# EVK-IRIS-W1-MCULINK-MUX.net
KiCad netlist of a schematic drawn in Altium Designer
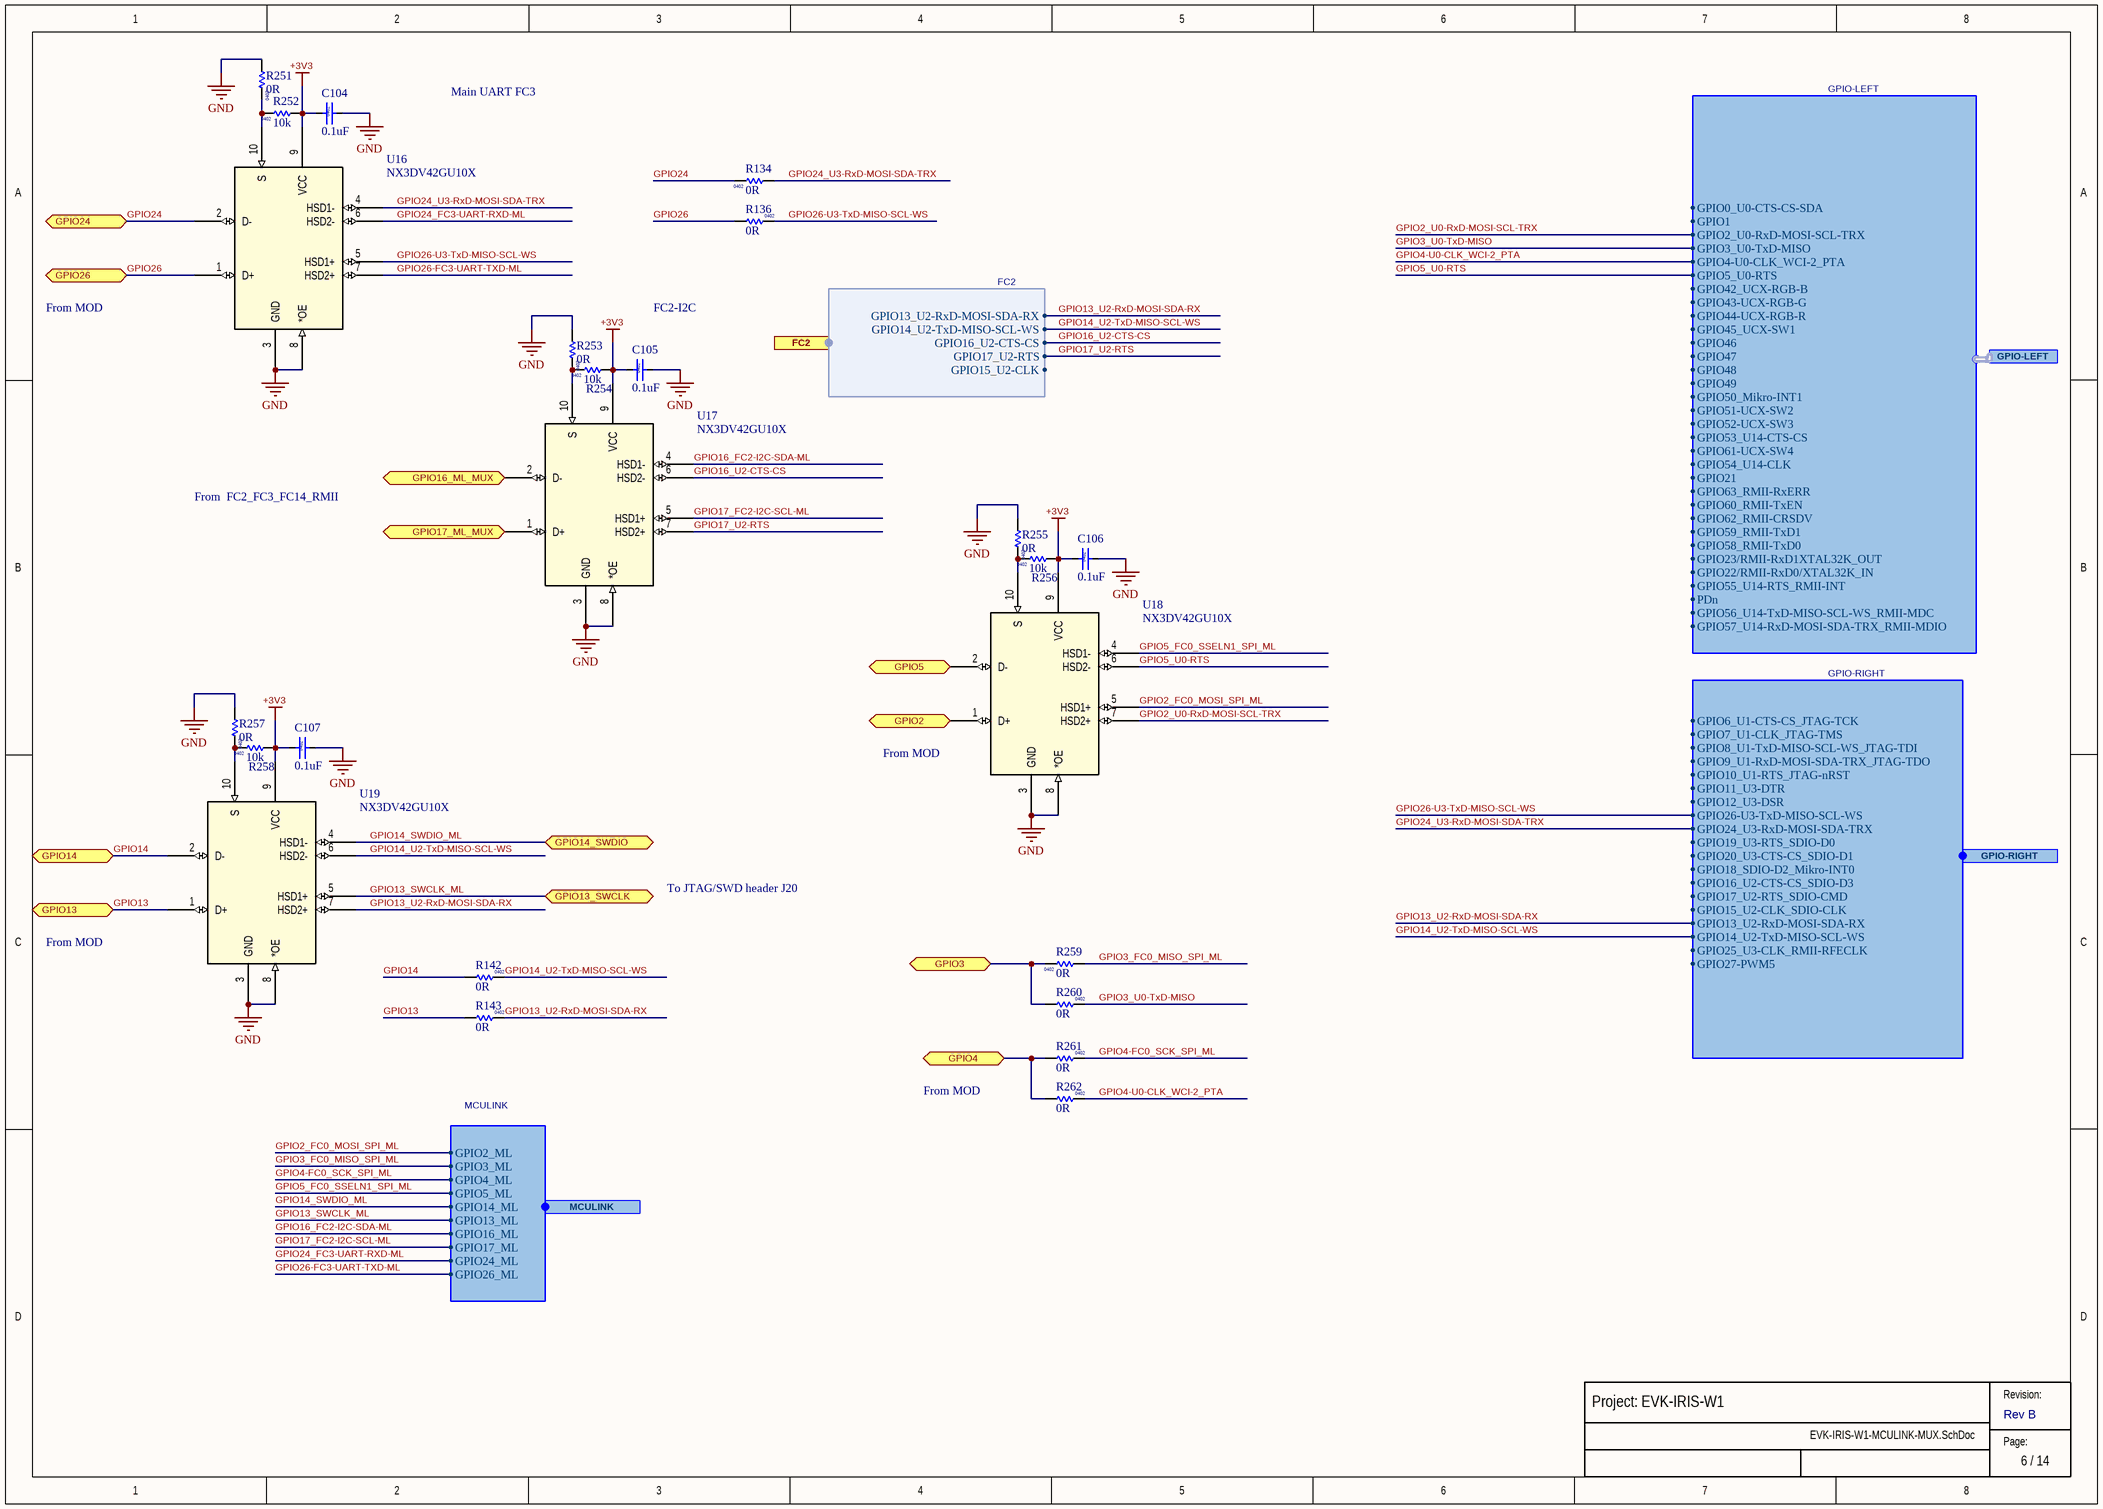
[diagram p0: EVK-IRIS-W1-MCULINK-MUX.SchDoc]

(export (version "E")
  (design (tool "Eeschema 10.0.6"))
  (components
    (comp (ref "C104")
      (value "0.1uF")
      (footprint "Cap 0402 HD")
      (description "Cap, Ceramic 0.1uF 10V 10% X5R 0402")
      (fields
        (field (name "SIZE") "0402")
        (field (name "PART NUMBER") "120-00016")
        (field (name "TOLERANCE") "+/- 10%")
      )
      (libsource (lib "Arena_Parts_DB_Lib") (part "Cap Chip"))
    )
    (comp (ref "C105")
      (value "0.1uF")
      (footprint "Cap 0402 HD")
      (description "Cap, Ceramic 0.1uF 10V 10% X5R 0402")
      (fields
        (field (name "SIZE") "0402")
        (field (name "PART NUMBER") "120-00016")
        (field (name "TOLERANCE") "+/- 10%")
      )
      (libsource (lib "Arena_Parts_DB_Lib") (part "Cap Chip"))
    )
    (comp (ref "C106")
      (value "0.1uF")
      (footprint "Cap 0402 HD")
      (description "Cap, Ceramic 0.1uF 10V 10% X5R 0402")
      (fields
        (field (name "SIZE") "0402")
        (field (name "PART NUMBER") "120-00016")
        (field (name "TOLERANCE") "+/- 10%")
      )
      (libsource (lib "Arena_Parts_DB_Lib") (part "Cap Chip"))
    )
    (comp (ref "C107")
      (value "0.1uF")
      (footprint "Cap 0402 HD")
      (description "Cap, Ceramic 0.1uF 10V 10% X5R 0402")
      (fields
        (field (name "SIZE") "0402")
        (field (name "PART NUMBER") "120-00016")
        (field (name "TOLERANCE") "+/- 10%")
      )
      (libsource (lib "Arena_Parts_DB_Lib") (part "Cap Chip"))
    )
    (comp (ref "R134")
      (value "0R")
      (footprint "RES 0402 HD")
      (description "RES THICK FILM CHIP 0402 0R 0 100mW")
      (fields
        (field (name "SIZE") "0402")
        (field (name "PART NUMBER") "UBXH18-0003002")
        (field (name "TOLERANCE") "0")
        (field (name "EDITOR") "charlotte.biber")
        (field (name "RELEASED BY") "peter.mueller")
      )
      (libsource (lib "UBX_Parts_DB_Lib") (part "Res sm"))
    )
    (comp (ref "R136")
      (value "0R")
      (footprint "RES 0402 HD")
      (description "RES THICK FILM CHIP 0402 0R 0 100mW")
      (fields
        (field (name "SIZE") "0402")
        (field (name "PART NUMBER") "UBXH18-0003002")
        (field (name "TOLERANCE") "0")
        (field (name "EDITOR") "charlotte.biber")
        (field (name "RELEASED BY") "peter.mueller")
      )
      (libsource (lib "UBX_Parts_DB_Lib") (part "Res sm"))
    )
    (comp (ref "R142")
      (value "0R")
      (footprint "RES 0402 HD")
      (description "RES THICK FILM CHIP 0402 0R 0 100mW")
      (fields
        (field (name "SIZE") "0402")
        (field (name "PART NUMBER") "UBXH18-0003002")
        (field (name "TOLERANCE") "0")
        (field (name "EDITOR") "charlotte.biber")
        (field (name "RELEASED BY") "peter.mueller")
      )
      (libsource (lib "UBX_Parts_DB_Lib") (part "Res sm"))
    )
    (comp (ref "R143")
      (value "0R")
      (footprint "RES 0402 HD")
      (description "RES THICK FILM CHIP 0402 0R 0 100mW")
      (fields
        (field (name "SIZE") "0402")
        (field (name "PART NUMBER") "UBXH18-0003002")
        (field (name "TOLERANCE") "0")
        (field (name "EDITOR") "charlotte.biber")
        (field (name "RELEASED BY") "peter.mueller")
      )
      (libsource (lib "UBX_Parts_DB_Lib") (part "Res sm"))
    )
    (comp (ref "R251")
      (value "0R")
      (footprint "RES 0402 HD")
      (description "RES THICK FILM CHIP 0402 0R 0 100mW")
      (fields
        (field (name "SIZE") "0402")
        (field (name "PART NUMBER") "UBXH18-0003002")
        (field (name "TOLERANCE") "0")
        (field (name "EDITOR") "charlotte.biber")
        (field (name "RELEASED BY") "peter.mueller")
      )
      (libsource (lib "UBX_Parts_DB_Lib") (part "Res sm"))
    )
    (comp (ref "R252")
      (value "10k")
      (footprint "RES 0402 HD")
      (description "Resistor 10k ohm 1% 1/16W, 0402")
      (fields
        (field (name "SIZE") "0402")
        (field (name "PART NUMBER") "180-00024")
        (field (name "POWER") "1/16W")
      )
      (libsource (lib "Arena_Parts_DB_Lib") (part "Res sm"))
    )
    (comp (ref "R253")
      (value "0R")
      (footprint "RES 0402 HD")
      (description "RES THICK FILM CHIP 0402 0R 0 100mW")
      (fields
        (field (name "SIZE") "0402")
        (field (name "PART NUMBER") "UBXH18-0003002")
        (field (name "TOLERANCE") "0")
        (field (name "EDITOR") "charlotte.biber")
        (field (name "RELEASED BY") "peter.mueller")
      )
      (libsource (lib "UBX_Parts_DB_Lib") (part "Res sm"))
    )
    (comp (ref "R254")
      (value "10k")
      (footprint "RES 0402 HD")
      (description "Resistor 10k ohm 1% 1/16W, 0402")
      (fields
        (field (name "SIZE") "0402")
        (field (name "PART NUMBER") "180-00024")
        (field (name "POWER") "1/16W")
      )
      (libsource (lib "Arena_Parts_DB_Lib") (part "Res sm"))
    )
    (comp (ref "R255")
      (value "0R")
      (footprint "RES 0402 HD")
      (description "RES THICK FILM CHIP 0402 0R 0 100mW")
      (fields
        (field (name "SIZE") "0402")
        (field (name "PART NUMBER") "UBXH18-0003002")
        (field (name "TOLERANCE") "0")
        (field (name "EDITOR") "charlotte.biber")
        (field (name "RELEASED BY") "peter.mueller")
      )
      (libsource (lib "UBX_Parts_DB_Lib") (part "Res sm"))
    )
    (comp (ref "R256")
      (value "10k")
      (footprint "RES 0402 HD")
      (description "Resistor 10k ohm 1% 1/16W, 0402")
      (fields
        (field (name "SIZE") "0402")
        (field (name "PART NUMBER") "180-00024")
        (field (name "POWER") "1/16W")
      )
      (libsource (lib "Arena_Parts_DB_Lib") (part "Res sm"))
    )
    (comp (ref "R257")
      (value "0R")
      (footprint "RES 0402 HD")
      (description "RES THICK FILM CHIP 0402 0R 0 100mW")
      (fields
        (field (name "SIZE") "0402")
        (field (name "PART NUMBER") "UBXH18-0003002")
        (field (name "TOLERANCE") "0")
        (field (name "EDITOR") "charlotte.biber")
        (field (name "RELEASED BY") "peter.mueller")
      )
      (libsource (lib "UBX_Parts_DB_Lib") (part "Res sm"))
    )
    (comp (ref "R258")
      (value "10k")
      (footprint "RES 0402 HD")
      (description "Resistor 10k ohm 1% 1/16W, 0402")
      (fields
        (field (name "SIZE") "0402")
        (field (name "PART NUMBER") "180-00024")
        (field (name "POWER") "1/16W")
      )
      (libsource (lib "Arena_Parts_DB_Lib") (part "Res sm"))
    )
    (comp (ref "R259")
      (value "0R")
      (footprint "RES 0402 HD")
      (description "RES THICK FILM CHIP 0402 0R 0 100mW")
      (fields
        (field (name "SIZE") "0402")
        (field (name "PART NUMBER") "UBXH18-0003002")
        (field (name "TOLERANCE") "0")
        (field (name "EDITOR") "charlotte.biber")
        (field (name "RELEASED BY") "peter.mueller")
      )
      (libsource (lib "UBX_Parts_DB_Lib") (part "Res sm"))
    )
    (comp (ref "R260")
      (value "0R")
      (footprint "RES 0402 HD")
      (description "RES THICK FILM CHIP 0402 0R 0 100mW")
      (fields
        (field (name "SIZE") "0402")
        (field (name "PART NUMBER") "UBXH18-0003002")
        (field (name "TOLERANCE") "0")
        (field (name "EDITOR") "charlotte.biber")
        (field (name "RELEASED BY") "peter.mueller")
      )
      (libsource (lib "UBX_Parts_DB_Lib") (part "Res sm"))
    )
    (comp (ref "R261")
      (value "0R")
      (footprint "RES 0402 HD")
      (description "RES THICK FILM CHIP 0402 0R 0 100mW")
      (fields
        (field (name "SIZE") "0402")
        (field (name "PART NUMBER") "UBXH18-0003002")
        (field (name "TOLERANCE") "0")
        (field (name "EDITOR") "charlotte.biber")
        (field (name "RELEASED BY") "peter.mueller")
      )
      (libsource (lib "UBX_Parts_DB_Lib") (part "Res sm"))
    )
    (comp (ref "R262")
      (value "0R")
      (footprint "RES 0402 HD")
      (description "RES THICK FILM CHIP 0402 0R 0 100mW")
      (fields
        (field (name "SIZE") "0402")
        (field (name "PART NUMBER") "UBXH18-0003002")
        (field (name "TOLERANCE") "0")
        (field (name "EDITOR") "charlotte.biber")
        (field (name "RELEASED BY") "peter.mueller")
      )
      (libsource (lib "UBX_Parts_DB_Lib") (part "Res sm"))
    )
    (comp (ref "U16")
      (value "NX3DV42GU10X")
      (footprint "XQFN10_SOT1337-1_NXP")
      (description "No Description Available")
      (fields (field (name "COPYRIGHT") "Copyright (C) 2023 Ultra Librarian. All rights reserved."))
      (libsource (lib "NX3DV42GU10X") (part "NX3DV42GU10X"))
    )
    (comp (ref "U17")
      (value "NX3DV42GU10X")
      (footprint "XQFN10_SOT1337-1_NXP")
      (description "No Description Available")
      (fields (field (name "COPYRIGHT") "Copyright (C) 2023 Ultra Librarian. All rights reserved."))
      (libsource (lib "NX3DV42GU10X") (part "NX3DV42GU10X"))
    )
    (comp (ref "U18")
      (value "NX3DV42GU10X")
      (footprint "XQFN10_SOT1337-1_NXP")
      (description "No Description Available")
      (fields (field (name "COPYRIGHT") "Copyright (C) 2023 Ultra Librarian. All rights reserved."))
      (libsource (lib "NX3DV42GU10X") (part "NX3DV42GU10X"))
    )
    (comp (ref "U19")
      (value "NX3DV42GU10X")
      (footprint "XQFN10_SOT1337-1_NXP")
      (description "No Description Available")
      (fields (field (name "COPYRIGHT") "Copyright (C) 2023 Ultra Librarian. All rights reserved."))
      (libsource (lib "NX3DV42GU10X") (part "NX3DV42GU10X"))
    )
  )
  (nets
    (net (code "5") (name "+3V3") (class "Default")
      (node (ref "C104") (pin "1") (pinfunction "1_1") (pintype "passive"))
      (node (ref "C105") (pin "1") (pinfunction "1_1") (pintype "passive"))
      (node (ref "C106") (pin "1") (pinfunction "1_1") (pintype "passive"))
      (node (ref "C107") (pin "1") (pinfunction "1_1") (pintype "passive"))
      (node (ref "R252") (pin "1") (pinfunction "1_1") (pintype "passive"))
      (node (ref "R254") (pin "1") (pinfunction "1_1") (pintype "passive"))
      (node (ref "R256") (pin "1") (pinfunction "1_1") (pintype "passive"))
      (node (ref "R258") (pin "1") (pinfunction "1_1") (pintype "passive"))
      (node (ref "U16") (pin "9") (pinfunction "VCC_9") (pintype "power_in"))
      (node (ref "U17") (pin "9") (pinfunction "VCC_9") (pintype "power_in"))
      (node (ref "U18") (pin "9") (pinfunction "VCC_9") (pintype "power_in"))
      (node (ref "U19") (pin "9") (pinfunction "VCC_9") (pintype "power_in"))
    )
    (net (code "6") (name "/GPIO2") (class "Default")
      (node (ref "U18") (pin "1") (pinfunction "D+_1") (pintype "bidirectional"))
    )
    (net (code "7") (name "/GPIO2_FC0_MOSI_SPI_ML") (class "Default")
      (node (ref "U18") (pin "5") (pinfunction "HSD1+_5") (pintype "bidirectional"))
    )
    (net (code "8") (name "/GPIO2_U0-RxD-MOSI-SCL-TRX") (class "Default")
      (node (ref "U18") (pin "7") (pinfunction "HSD2+_7") (pintype "bidirectional"))
    )
    (net (code "9") (name "/GPIO3") (class "Default")
      (node (ref "R259") (pin "2") (pinfunction "2_2") (pintype "passive"))
      (node (ref "R260") (pin "1") (pinfunction "1_1") (pintype "passive"))
    )
    (net (code "10") (name "/GPIO3_FC0_MISO_SPI_ML") (class "Default")
      (node (ref "R259") (pin "1") (pinfunction "1_1") (pintype "passive"))
    )
    (net (code "11") (name "/GPIO3_U0-TxD-MISO") (class "Default")
      (node (ref "R260") (pin "2") (pinfunction "2_2") (pintype "passive"))
    )
    (net (code "12") (name "/GPIO4") (class "Default")
      (node (ref "R261") (pin "1") (pinfunction "1_1") (pintype "passive"))
      (node (ref "R262") (pin "1") (pinfunction "1_1") (pintype "passive"))
    )
    (net (code "13") (name "/GPIO4-FC0_SCK_SPI_ML") (class "Default")
      (node (ref "R261") (pin "2") (pinfunction "2_2") (pintype "passive"))
    )
    (net (code "14") (name "/GPIO4-U0-CLK_WCI-2_PTA") (class "Default")
      (node (ref "R262") (pin "2") (pinfunction "2_2") (pintype "passive"))
    )
    (net (code "15") (name "/GPIO5") (class "Default")
      (node (ref "U18") (pin "2") (pinfunction "D-_2") (pintype "bidirectional"))
    )
    (net (code "16") (name "/GPIO5_FC0_SSELN1_SPI_ML") (class "Default")
      (node (ref "U18") (pin "4") (pinfunction "HSD1-_4") (pintype "bidirectional"))
    )
    (net (code "17") (name "/GPIO5_U0-RTS") (class "Default")
      (node (ref "U18") (pin "6") (pinfunction "HSD2-_6") (pintype "bidirectional"))
    )
    (net (code "18") (name "/GPIO13") (class "Default")
      (node (ref "R143") (pin "1") (pinfunction "1_1") (pintype "passive"))
      (node (ref "U19") (pin "1") (pinfunction "D+_1") (pintype "bidirectional"))
    )
    (net (code "19") (name "/GPIO13_SWCLK_ML") (class "Default")
      (node (ref "U19") (pin "5") (pinfunction "HSD1+_5") (pintype "bidirectional"))
    )
    (net (code "20") (name "/GPIO13_U2-RxD-MOSI-SDA-RX") (class "Default")
      (node (ref "R143") (pin "2") (pinfunction "2_2") (pintype "passive"))
      (node (ref "U19") (pin "7") (pinfunction "HSD2+_7") (pintype "bidirectional"))
    )
    (net (code "21") (name "/GPIO14") (class "Default")
      (node (ref "R142") (pin "1") (pinfunction "1_1") (pintype "passive"))
      (node (ref "U19") (pin "2") (pinfunction "D-_2") (pintype "bidirectional"))
    )
    (net (code "22") (name "/GPIO14_SWDIO_ML") (class "Default")
      (node (ref "U19") (pin "4") (pinfunction "HSD1-_4") (pintype "bidirectional"))
    )
    (net (code "23") (name "/GPIO14_U2-TxD-MISO-SCL-WS") (class "Default")
      (node (ref "R142") (pin "2") (pinfunction "2_2") (pintype "passive"))
      (node (ref "U19") (pin "6") (pinfunction "HSD2-_6") (pintype "bidirectional"))
    )
    (net (code "24") (name "/GPIO16_FC2-I2C-SDA-ML") (class "Default")
      (node (ref "U17") (pin "4") (pinfunction "HSD1-_4") (pintype "bidirectional"))
    )
    (net (code "25") (name "/GPIO16_ML_MUX") (class "Default")
      (node (ref "U17") (pin "2") (pinfunction "D-_2") (pintype "bidirectional"))
    )
    (net (code "26") (name "/GPIO16_U2-CTS-CS") (class "Default")
      (node (ref "U17") (pin "6") (pinfunction "HSD2-_6") (pintype "bidirectional"))
    )
    (net (code "27") (name "/GPIO17_FC2-I2C-SCL-ML") (class "Default")
      (node (ref "U17") (pin "5") (pinfunction "HSD1+_5") (pintype "bidirectional"))
    )
    (net (code "28") (name "/GPIO17_ML_MUX") (class "Default")
      (node (ref "U17") (pin "1") (pinfunction "D+_1") (pintype "bidirectional"))
    )
    (net (code "29") (name "/GPIO17_U2-RTS") (class "Default")
      (node (ref "U17") (pin "7") (pinfunction "HSD2+_7") (pintype "bidirectional"))
    )
    (net (code "30") (name "/GPIO24") (class "Default")
      (node (ref "R134") (pin "2") (pinfunction "2_2") (pintype "passive"))
      (node (ref "U16") (pin "2") (pinfunction "D-_2") (pintype "bidirectional"))
    )
    (net (code "31") (name "/GPIO24_FC3-UART-RXD-ML") (class "Default")
      (node (ref "U16") (pin "6") (pinfunction "HSD2-_6") (pintype "bidirectional"))
    )
    (net (code "32") (name "/GPIO24_U3-RxD-MOSI-SDA-TRX") (class "Default")
      (node (ref "R134") (pin "1") (pinfunction "1_1") (pintype "passive"))
      (node (ref "U16") (pin "4") (pinfunction "HSD1-_4") (pintype "bidirectional"))
    )
    (net (code "33") (name "/GPIO26") (class "Default")
      (node (ref "R136") (pin "1") (pinfunction "1_1") (pintype "passive"))
      (node (ref "U16") (pin "1") (pinfunction "D+_1") (pintype "bidirectional"))
    )
    (net (code "34") (name "/GPIO26-FC3-UART-TXD-ML") (class "Default")
      (node (ref "U16") (pin "7") (pinfunction "HSD2+_7") (pintype "bidirectional"))
    )
    (net (code "35") (name "/GPIO26-U3-TxD-MISO-SCL-WS") (class "Default")
      (node (ref "R136") (pin "2") (pinfunction "2_2") (pintype "passive"))
      (node (ref "U16") (pin "5") (pinfunction "HSD1+_5") (pintype "bidirectional"))
    )
    (net (code "40") (name "GND") (class "Default")
      (node (ref "C104") (pin "2") (pinfunction "2_2") (pintype "passive"))
      (node (ref "C105") (pin "2") (pinfunction "2_2") (pintype "passive"))
      (node (ref "C106") (pin "2") (pinfunction "2_2") (pintype "passive"))
      (node (ref "C107") (pin "2") (pinfunction "2_2") (pintype "passive"))
      (node (ref "R251") (pin "1") (pinfunction "1_1") (pintype "passive"))
      (node (ref "R253") (pin "1") (pinfunction "1_1") (pintype "passive"))
      (node (ref "R255") (pin "1") (pinfunction "1_1") (pintype "passive"))
      (node (ref "R257") (pin "1") (pinfunction "1_1") (pintype "passive"))
      (node (ref "U16") (pin "3") (pinfunction "GND_3") (pintype "passive"))
      (node (ref "U16") (pin "8") (pinfunction "*OE_8") (pintype "input"))
      (node (ref "U17") (pin "3") (pinfunction "GND_3") (pintype "passive"))
      (node (ref "U17") (pin "8") (pinfunction "*OE_8") (pintype "input"))
      (node (ref "U18") (pin "3") (pinfunction "GND_3") (pintype "passive"))
      (node (ref "U18") (pin "8") (pinfunction "*OE_8") (pintype "input"))
      (node (ref "U19") (pin "3") (pinfunction "GND_3") (pintype "passive"))
      (node (ref "U19") (pin "8") (pinfunction "*OE_8") (pintype "input"))
    )
    (net (code "41") (name "Net-(U16-S)") (class "Default")
      (node (ref "R251") (pin "2") (pinfunction "2_2") (pintype "passive"))
      (node (ref "R252") (pin "2") (pinfunction "2_2") (pintype "passive"))
      (node (ref "U16") (pin "10") (pinfunction "S_10") (pintype "input"))
    )
    (net (code "42") (name "Net-(U17-S)") (class "Default")
      (node (ref "R253") (pin "2") (pinfunction "2_2") (pintype "passive"))
      (node (ref "R254") (pin "2") (pinfunction "2_2") (pintype "passive"))
      (node (ref "U17") (pin "10") (pinfunction "S_10") (pintype "input"))
    )
    (net (code "43") (name "Net-(U18-S)") (class "Default")
      (node (ref "R255") (pin "2") (pinfunction "2_2") (pintype "passive"))
      (node (ref "R256") (pin "2") (pinfunction "2_2") (pintype "passive"))
      (node (ref "U18") (pin "10") (pinfunction "S_10") (pintype "input"))
    )
    (net (code "44") (name "Net-(U19-S)") (class "Default")
      (node (ref "R257") (pin "2") (pinfunction "2_2") (pintype "passive"))
      (node (ref "R258") (pin "2") (pinfunction "2_2") (pintype "passive"))
      (node (ref "U19") (pin "10") (pinfunction "S_10") (pintype "input"))
    )
  )
)
